# 2AD66-ufl.net
KiCad netlist of a schematic drawn in EAGLE
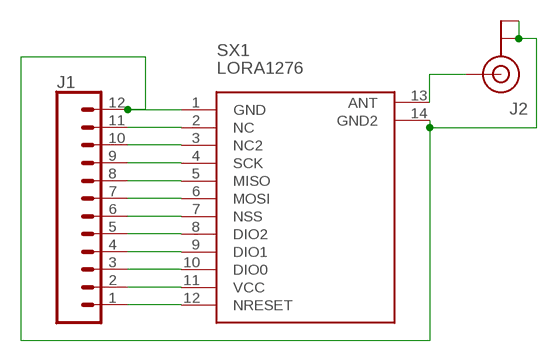
[diagram p0: schematic, sheet 1]

(export (version "E")
  (design (tool "Eeschema 10.0.6"))
  (components
    (comp (ref "J1")
      (value "CONN_12")
      (footprint "eagle-import:1X12")
      (libsource (lib "eagle-import") (part "CONN_12"))
    )
    (comp (ref "J2")
      (value "U.FL")
      (footprint "eagle-import:U.FL")
      (libsource (lib "eagle-import") (part "U.FL"))
    )
    (comp (ref "SX1")
      (value "LORA1276")
      (footprint "eagle-import:PCBV2")
      (libsource (lib "eagle-import") (part "LORA1276"))
    )
  )
  (nets
    (net (code "1") (name "Net-(J2-SIGNAL)") (class "Default")
      (node (ref "J2") (pin "FEED") (pinfunction "SIGNAL_FEED") (pintype "bidirectional"))
      (node (ref "SX1") (pin "13") (pinfunction "ANT_13") (pintype "bidirectional"))
    )
    (net (code "2") (name "Net-(SX1-DIO0)") (class "Default")
      (node (ref "J1") (pin "3") (pinfunction "3_3") (pintype "passive"))
      (node (ref "SX1") (pin "10") (pinfunction "DIO0_10") (pintype "bidirectional"))
    )
    (net (code "3") (name "Net-(SX1-DIO1)") (class "Default")
      (node (ref "J1") (pin "4") (pinfunction "4_4") (pintype "passive"))
      (node (ref "SX1") (pin "9") (pinfunction "DIO1_9") (pintype "bidirectional"))
    )
    (net (code "4") (name "Net-(SX1-DIO2)") (class "Default")
      (node (ref "J1") (pin "5") (pinfunction "5_5") (pintype "passive"))
      (node (ref "SX1") (pin "8") (pinfunction "DIO2_8") (pintype "bidirectional"))
    )
    (net (code "5") (name "Net-(SX1-GND)") (class "Default")
      (node (ref "J1") (pin "12") (pinfunction "12_12") (pintype "passive"))
      (node (ref "J2") (pin "1") (pinfunction "GND_1") (pintype "bidirectional"))
      (node (ref "J2") (pin "2") (pinfunction "GND_2") (pintype "bidirectional"))
      (node (ref "SX1") (pin "1") (pinfunction "GND_1") (pintype "bidirectional"))
      (node (ref "SX1") (pin "14") (pinfunction "GND2_14") (pintype "bidirectional"))
    )
    (net (code "6") (name "Net-(SX1-MISO)") (class "Default")
      (node (ref "J1") (pin "8") (pinfunction "8_8") (pintype "passive"))
      (node (ref "SX1") (pin "5") (pinfunction "MISO_5") (pintype "bidirectional"))
    )
    (net (code "7") (name "Net-(SX1-MOSI)") (class "Default")
      (node (ref "J1") (pin "7") (pinfunction "7_7") (pintype "passive"))
      (node (ref "SX1") (pin "6") (pinfunction "MOSI_6") (pintype "bidirectional"))
    )
    (net (code "8") (name "Net-(SX1-NC)") (class "Default")
      (node (ref "J1") (pin "11") (pinfunction "11_11") (pintype "passive"))
      (node (ref "SX1") (pin "2") (pinfunction "NC_2") (pintype "bidirectional"))
    )
    (net (code "9") (name "Net-(SX1-NC2)") (class "Default")
      (node (ref "J1") (pin "10") (pinfunction "10_10") (pintype "passive"))
      (node (ref "SX1") (pin "3") (pinfunction "NC2_3") (pintype "bidirectional"))
    )
    (net (code "10") (name "Net-(SX1-NRESET)") (class "Default")
      (node (ref "J1") (pin "1") (pinfunction "1_1") (pintype "passive"))
      (node (ref "SX1") (pin "12") (pinfunction "NRESET_12") (pintype "bidirectional"))
    )
    (net (code "11") (name "Net-(SX1-NSS)") (class "Default")
      (node (ref "J1") (pin "6") (pinfunction "6_6") (pintype "passive"))
      (node (ref "SX1") (pin "7") (pinfunction "NSS_7") (pintype "bidirectional"))
    )
    (net (code "12") (name "Net-(SX1-SCK)") (class "Default")
      (node (ref "J1") (pin "9") (pinfunction "9_9") (pintype "passive"))
      (node (ref "SX1") (pin "4") (pinfunction "SCK_4") (pintype "bidirectional"))
    )
    (net (code "13") (name "Net-(SX1-VCC)") (class "Default")
      (node (ref "J1") (pin "2") (pinfunction "2_2") (pintype "passive"))
      (node (ref "SX1") (pin "11") (pinfunction "VCC_11") (pintype "bidirectional"))
    )
  )
)
